# J1-3xGTHQ_R_B66.net
KiCad netlist of a schematic drawn in Altium Designer
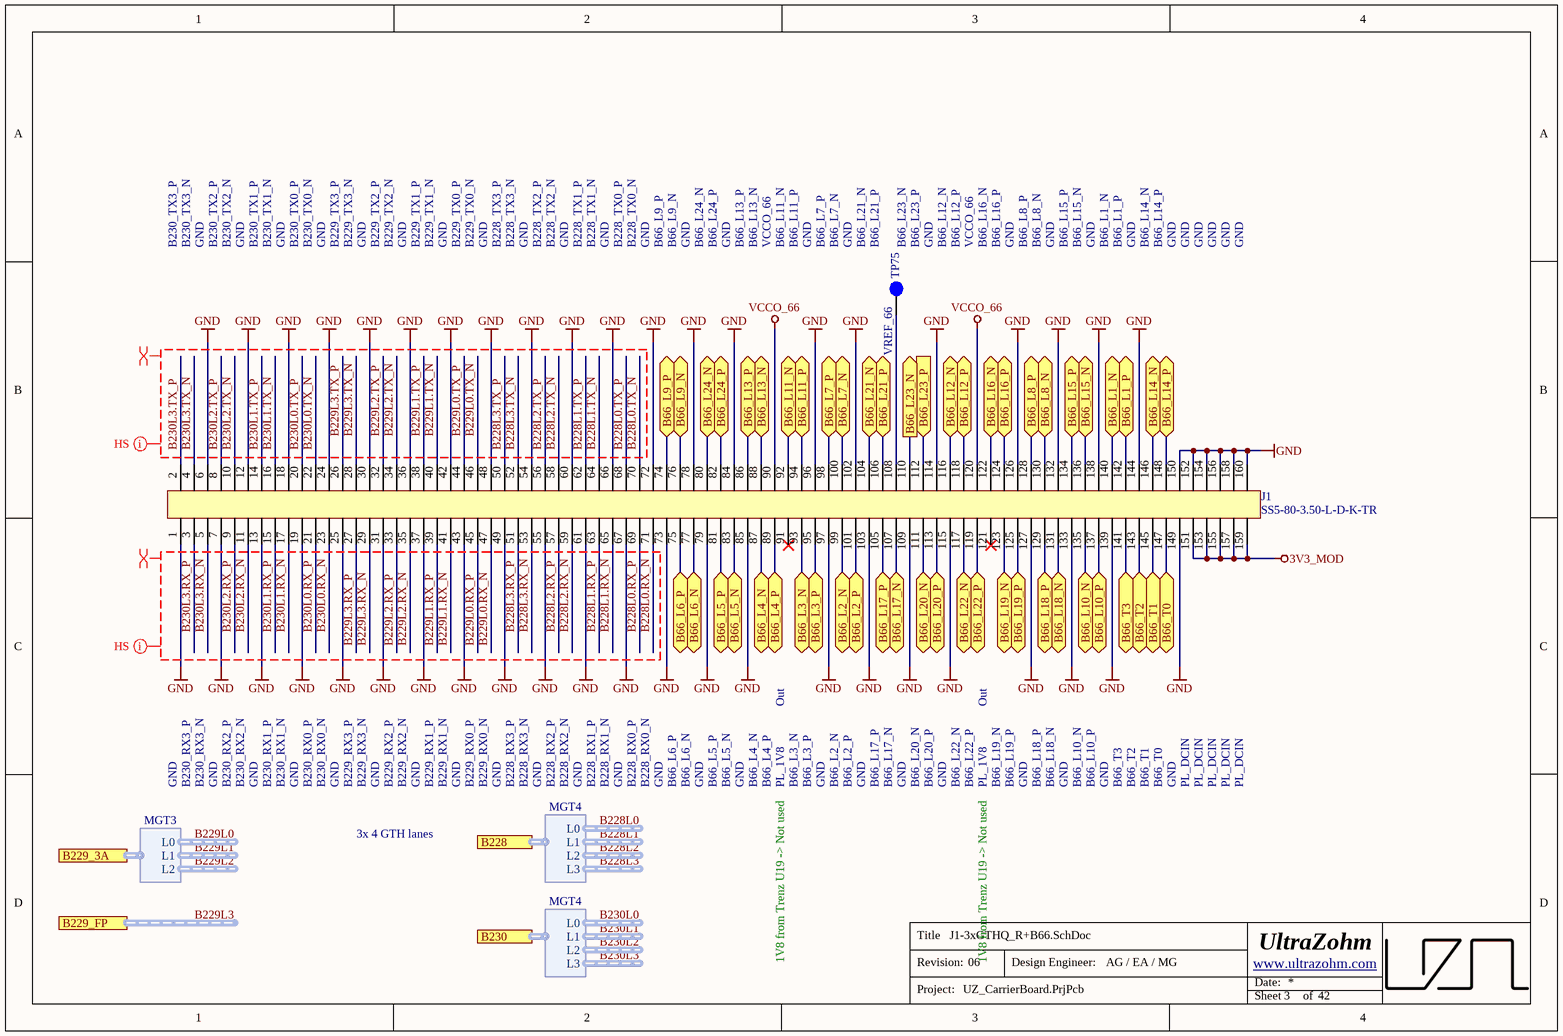
[diagram p0: J1-3xGTHQ_R+B66.SchDoc]

(export (version "E")
  (design (tool "Eeschema 10.0.6"))
  (components
    (comp (ref "J1")
      (value "SS5-80-3.50-L-D-K-TR")
      (footprint "SS5-80-3.50-L-D-K-TR")
      (description "0.5 mm Ultra Fine Pitch Socket REF192552-01, 160 Pins")
      (fields
        (field (name "MANUFACTURER") "SAMTEC")
        (field (name "LCSC PART NUMBER") "C5292077")
        (field (name "CREATED FROM") "MGremer")
      )
      (libsource (lib "user") (part "SS5-80-3.50-L-D-K-TR"))
    )
    (comp (ref "TP75") (value "Testpoint 1mm") (footprint "TP_1mm") (libsource (lib "TE") (part "TP")))
  )
  (nets
    (net (code "15") (name "/B66_L1_N") (class "Default")
      (node (ref "J1") (pin "140") (pinfunction "140_140") (pintype "passive"))
    )
    (net (code "16") (name "/B66_L1_P") (class "Default")
      (node (ref "J1") (pin "142") (pinfunction "142_142") (pintype "passive"))
    )
    (net (code "17") (name "/B66_L2_N") (class "Default")
      (node (ref "J1") (pin "99") (pinfunction "99_99") (pintype "passive"))
    )
    (net (code "18") (name "/B66_L2_P") (class "Default")
      (node (ref "J1") (pin "101") (pinfunction "101_101") (pintype "passive"))
    )
    (net (code "19") (name "/B66_L3_N") (class "Default")
      (node (ref "J1") (pin "93") (pinfunction "93_93") (pintype "passive"))
    )
    (net (code "20") (name "/B66_L3_P") (class "Default")
      (node (ref "J1") (pin "95") (pinfunction "95_95") (pintype "passive"))
    )
    (net (code "21") (name "/B66_L4_N") (class "Default")
      (node (ref "J1") (pin "87") (pinfunction "87_87") (pintype "passive"))
    )
    (net (code "22") (name "/B66_L4_P") (class "Default")
      (node (ref "J1") (pin "89") (pinfunction "89_89") (pintype "passive"))
    )
    (net (code "23") (name "/B66_L5_N") (class "Default")
      (node (ref "J1") (pin "83") (pinfunction "83_83") (pintype "passive"))
    )
    (net (code "24") (name "/B66_L5_P") (class "Default")
      (node (ref "J1") (pin "81") (pinfunction "81_81") (pintype "passive"))
    )
    (net (code "25") (name "/B66_L6_N") (class "Default")
      (node (ref "J1") (pin "77") (pinfunction "77_77") (pintype "passive"))
    )
    (net (code "26") (name "/B66_L6_P") (class "Default")
      (node (ref "J1") (pin "75") (pinfunction "75_75") (pintype "passive"))
    )
    (net (code "27") (name "/B66_L7_N") (class "Default")
      (node (ref "J1") (pin "100") (pinfunction "100_100") (pintype "passive"))
    )
    (net (code "28") (name "/B66_L7_P") (class "Default")
      (node (ref "J1") (pin "98") (pinfunction "98_98") (pintype "passive"))
    )
    (net (code "29") (name "/B66_L8_N") (class "Default")
      (node (ref "J1") (pin "130") (pinfunction "130_130") (pintype "passive"))
    )
    (net (code "30") (name "/B66_L8_P") (class "Default")
      (node (ref "J1") (pin "128") (pinfunction "128_128") (pintype "passive"))
    )
    (net (code "31") (name "/B66_L9_N") (class "Default")
      (node (ref "J1") (pin "76") (pinfunction "76_76") (pintype "passive"))
    )
    (net (code "32") (name "/B66_L9_P") (class "Default")
      (node (ref "J1") (pin "74") (pinfunction "74_74") (pintype "passive"))
    )
    (net (code "33") (name "/B66_L10_N") (class "Default")
      (node (ref "J1") (pin "135") (pinfunction "135_135") (pintype "passive"))
    )
    (net (code "34") (name "/B66_L10_P") (class "Default")
      (node (ref "J1") (pin "137") (pinfunction "137_137") (pintype "passive"))
    )
    (net (code "35") (name "/B66_L11_N") (class "Default")
      (node (ref "J1") (pin "92") (pinfunction "92_92") (pintype "passive"))
    )
    (net (code "36") (name "/B66_L11_P") (class "Default")
      (node (ref "J1") (pin "94") (pinfunction "94_94") (pintype "passive"))
    )
    (net (code "37") (name "/B66_L12_N") (class "Default")
      (node (ref "J1") (pin "116") (pinfunction "116_116") (pintype "passive"))
    )
    (net (code "38") (name "/B66_L12_P") (class "Default")
      (node (ref "J1") (pin "118") (pinfunction "118_118") (pintype "passive"))
    )
    (net (code "39") (name "/B66_L13_N") (class "Default")
      (node (ref "J1") (pin "88") (pinfunction "88_88") (pintype "passive"))
    )
    (net (code "40") (name "/B66_L13_P") (class "Default")
      (node (ref "J1") (pin "86") (pinfunction "86_86") (pintype "passive"))
    )
    (net (code "41") (name "/B66_L14_N") (class "Default")
      (node (ref "J1") (pin "146") (pinfunction "146_146") (pintype "passive"))
    )
    (net (code "42") (name "/B66_L14_P") (class "Default")
      (node (ref "J1") (pin "148") (pinfunction "148_148") (pintype "passive"))
    )
    (net (code "43") (name "/B66_L15_N") (class "Default")
      (node (ref "J1") (pin "136") (pinfunction "136_136") (pintype "passive"))
    )
    (net (code "44") (name "/B66_L15_P") (class "Default")
      (node (ref "J1") (pin "134") (pinfunction "134_134") (pintype "passive"))
    )
    (net (code "45") (name "/B66_L16_N") (class "Default")
      (node (ref "J1") (pin "122") (pinfunction "122_122") (pintype "passive"))
    )
    (net (code "46") (name "/B66_L16_P") (class "Default")
      (node (ref "J1") (pin "124") (pinfunction "124_124") (pintype "passive"))
    )
    (net (code "47") (name "/B66_L17_N") (class "Default")
      (node (ref "J1") (pin "107") (pinfunction "107_107") (pintype "passive"))
    )
    (net (code "48") (name "/B66_L17_P") (class "Default")
      (node (ref "J1") (pin "105") (pinfunction "105_105") (pintype "passive"))
    )
    (net (code "49") (name "/B66_L18_N") (class "Default")
      (node (ref "J1") (pin "131") (pinfunction "131_131") (pintype "passive"))
    )
    (net (code "50") (name "/B66_L18_P") (class "Default")
      (node (ref "J1") (pin "129") (pinfunction "129_129") (pintype "passive"))
    )
    (net (code "51") (name "/B66_L19_N") (class "Default")
      (node (ref "J1") (pin "123") (pinfunction "123_123") (pintype "passive"))
    )
    (net (code "52") (name "/B66_L19_P") (class "Default")
      (node (ref "J1") (pin "125") (pinfunction "125_125") (pintype "passive"))
    )
    (net (code "53") (name "/B66_L20_N") (class "Default")
      (node (ref "J1") (pin "111") (pinfunction "111_111") (pintype "passive"))
    )
    (net (code "54") (name "/B66_L20_P") (class "Default")
      (node (ref "J1") (pin "113") (pinfunction "113_113") (pintype "passive"))
    )
    (net (code "55") (name "/B66_L21_N") (class "Default")
      (node (ref "J1") (pin "104") (pinfunction "104_104") (pintype "passive"))
    )
    (net (code "56") (name "/B66_L21_P") (class "Default")
      (node (ref "J1") (pin "106") (pinfunction "106_106") (pintype "passive"))
    )
    (net (code "57") (name "/B66_L22_N") (class "Default")
      (node (ref "J1") (pin "117") (pinfunction "117_117") (pintype "passive"))
    )
    (net (code "58") (name "/B66_L22_P") (class "Default")
      (node (ref "J1") (pin "119") (pinfunction "119_119") (pintype "passive"))
    )
    (net (code "59") (name "/B66_L23_N") (class "Default")
      (node (ref "J1") (pin "110") (pinfunction "110_110") (pintype "passive"))
    )
    (net (code "60") (name "/B66_L23_P") (class "Default")
      (node (ref "J1") (pin "112") (pinfunction "112_112") (pintype "passive"))
    )
    (net (code "61") (name "/B66_L24_N") (class "Default")
      (node (ref "J1") (pin "80") (pinfunction "80_80") (pintype "passive"))
    )
    (net (code "62") (name "/B66_L24_P") (class "Default")
      (node (ref "J1") (pin "82") (pinfunction "82_82") (pintype "passive"))
    )
    (net (code "63") (name "/B66_T0") (class "Default")
      (node (ref "J1") (pin "147") (pinfunction "147_147") (pintype "passive"))
    )
    (net (code "64") (name "/B66_T1") (class "Default")
      (node (ref "J1") (pin "145") (pinfunction "145_145") (pintype "passive"))
    )
    (net (code "65") (name "/B66_T2") (class "Default")
      (node (ref "J1") (pin "143") (pinfunction "143_143") (pintype "passive"))
    )
    (net (code "66") (name "/B66_T3") (class "Default")
      (node (ref "J1") (pin "141") (pinfunction "141_141") (pintype "passive"))
    )
    (net (code "67") (name "/B228L0.RX_N") (class "Default")
      (node (ref "J1") (pin "71") (pinfunction "71_71") (pintype "passive"))
    )
    (net (code "68") (name "/B228L0.RX_P") (class "Default")
      (node (ref "J1") (pin "69") (pinfunction "69_69") (pintype "passive"))
    )
    (net (code "69") (name "/B228L0.TX_N") (class "Default")
      (node (ref "J1") (pin "70") (pinfunction "70_70") (pintype "passive"))
    )
    (net (code "70") (name "/B228L0.TX_P") (class "Default")
      (node (ref "J1") (pin "68") (pinfunction "68_68") (pintype "passive"))
    )
    (net (code "72") (name "/B228L1.RX_N") (class "Default")
      (node (ref "J1") (pin "65") (pinfunction "65_65") (pintype "passive"))
    )
    (net (code "73") (name "/B228L1.RX_P") (class "Default")
      (node (ref "J1") (pin "63") (pinfunction "63_63") (pintype "passive"))
    )
    (net (code "74") (name "/B228L1.TX_N") (class "Default")
      (node (ref "J1") (pin "64") (pinfunction "64_64") (pintype "passive"))
    )
    (net (code "75") (name "/B228L1.TX_P") (class "Default")
      (node (ref "J1") (pin "62") (pinfunction "62_62") (pintype "passive"))
    )
    (net (code "76") (name "/B228L2.RX_N") (class "Default")
      (node (ref "J1") (pin "59") (pinfunction "59_59") (pintype "passive"))
    )
    (net (code "77") (name "/B228L2.RX_P") (class "Default")
      (node (ref "J1") (pin "57") (pinfunction "57_57") (pintype "passive"))
    )
    (net (code "78") (name "/B228L2.TX_N") (class "Default")
      (node (ref "J1") (pin "58") (pinfunction "58_58") (pintype "passive"))
    )
    (net (code "79") (name "/B228L2.TX_P") (class "Default")
      (node (ref "J1") (pin "56") (pinfunction "56_56") (pintype "passive"))
    )
    (net (code "80") (name "/B228L3.RX_N") (class "Default")
      (node (ref "J1") (pin "53") (pinfunction "53_53") (pintype "passive"))
    )
    (net (code "81") (name "/B228L3.RX_P") (class "Default")
      (node (ref "J1") (pin "51") (pinfunction "51_51") (pintype "passive"))
    )
    (net (code "82") (name "/B228L3.TX_N") (class "Default")
      (node (ref "J1") (pin "52") (pinfunction "52_52") (pintype "passive"))
    )
    (net (code "83") (name "/B228L3.TX_P") (class "Default")
      (node (ref "J1") (pin "50") (pinfunction "50_50") (pintype "passive"))
    )
    (net (code "85") (name "/B229L0.RX_N") (class "Default")
      (node (ref "J1") (pin "47") (pinfunction "47_47") (pintype "passive"))
    )
    (net (code "86") (name "/B229L0.RX_P") (class "Default")
      (node (ref "J1") (pin "45") (pinfunction "45_45") (pintype "passive"))
    )
    (net (code "87") (name "/B229L0.TX_N") (class "Default")
      (node (ref "J1") (pin "46") (pinfunction "46_46") (pintype "passive"))
    )
    (net (code "88") (name "/B229L0.TX_P") (class "Default")
      (node (ref "J1") (pin "44") (pinfunction "44_44") (pintype "passive"))
    )
    (net (code "89") (name "/B229L1.RX_N") (class "Default")
      (node (ref "J1") (pin "41") (pinfunction "41_41") (pintype "passive"))
    )
    (net (code "90") (name "/B229L1.RX_P") (class "Default")
      (node (ref "J1") (pin "39") (pinfunction "39_39") (pintype "passive"))
    )
    (net (code "91") (name "/B229L1.TX_N") (class "Default")
      (node (ref "J1") (pin "40") (pinfunction "40_40") (pintype "passive"))
    )
    (net (code "92") (name "/B229L1.TX_P") (class "Default")
      (node (ref "J1") (pin "38") (pinfunction "38_38") (pintype "passive"))
    )
    (net (code "93") (name "/B229L2.RX_N") (class "Default")
      (node (ref "J1") (pin "35") (pinfunction "35_35") (pintype "passive"))
    )
    (net (code "94") (name "/B229L2.RX_P") (class "Default")
      (node (ref "J1") (pin "33") (pinfunction "33_33") (pintype "passive"))
    )
    (net (code "95") (name "/B229L2.TX_N") (class "Default")
      (node (ref "J1") (pin "34") (pinfunction "34_34") (pintype "passive"))
    )
    (net (code "96") (name "/B229L2.TX_P") (class "Default")
      (node (ref "J1") (pin "32") (pinfunction "32_32") (pintype "passive"))
    )
    (net (code "98") (name "/B229L3.RX_N") (class "Default")
      (node (ref "J1") (pin "29") (pinfunction "29_29") (pintype "passive"))
    )
    (net (code "99") (name "/B229L3.RX_P") (class "Default")
      (node (ref "J1") (pin "27") (pinfunction "27_27") (pintype "passive"))
    )
    (net (code "100") (name "/B229L3.TX_N") (class "Default")
      (node (ref "J1") (pin "28") (pinfunction "28_28") (pintype "passive"))
    )
    (net (code "101") (name "/B229L3.TX_P") (class "Default")
      (node (ref "J1") (pin "26") (pinfunction "26_26") (pintype "passive"))
    )
    (net (code "103") (name "/B230L0.RX_N") (class "Default")
      (node (ref "J1") (pin "23") (pinfunction "23_23") (pintype "passive"))
    )
    (net (code "104") (name "/B230L0.RX_P") (class "Default")
      (node (ref "J1") (pin "21") (pinfunction "21_21") (pintype "passive"))
    )
    (net (code "105") (name "/B230L0.TX_N") (class "Default")
      (node (ref "J1") (pin "22") (pinfunction "22_22") (pintype "passive"))
    )
    (net (code "106") (name "/B230L0.TX_P") (class "Default")
      (node (ref "J1") (pin "20") (pinfunction "20_20") (pintype "passive"))
    )
    (net (code "108") (name "/B230L1.RX_N") (class "Default")
      (node (ref "J1") (pin "17") (pinfunction "17_17") (pintype "passive"))
    )
    (net (code "109") (name "/B230L1.RX_P") (class "Default")
      (node (ref "J1") (pin "15") (pinfunction "15_15") (pintype "passive"))
    )
    (net (code "110") (name "/B230L1.TX_N") (class "Default")
      (node (ref "J1") (pin "16") (pinfunction "16_16") (pintype "passive"))
    )
    (net (code "111") (name "/B230L1.TX_P") (class "Default")
      (node (ref "J1") (pin "14") (pinfunction "14_14") (pintype "passive"))
    )
    (net (code "112") (name "/B230L2.RX_N") (class "Default")
      (node (ref "J1") (pin "11") (pinfunction "11_11") (pintype "passive"))
    )
    (net (code "113") (name "/B230L2.RX_P") (class "Default")
      (node (ref "J1") (pin "9") (pinfunction "9_9") (pintype "passive"))
    )
    (net (code "114") (name "/B230L2.TX_N") (class "Default")
      (node (ref "J1") (pin "10") (pinfunction "10_10") (pintype "passive"))
    )
    (net (code "115") (name "/B230L2.TX_P") (class "Default")
      (node (ref "J1") (pin "8") (pinfunction "8_8") (pintype "passive"))
    )
    (net (code "116") (name "/B230L3.RX_N") (class "Default")
      (node (ref "J1") (pin "5") (pinfunction "5_5") (pintype "passive"))
    )
    (net (code "117") (name "/B230L3.RX_P") (class "Default")
      (node (ref "J1") (pin "3") (pinfunction "3_3") (pintype "passive"))
    )
    (net (code "118") (name "/B230L3.TX_N") (class "Default")
      (node (ref "J1") (pin "4") (pinfunction "4_4") (pintype "passive"))
    )
    (net (code "119") (name "/B230L3.TX_P") (class "Default")
      (node (ref "J1") (pin "2") (pinfunction "2_2") (pintype "passive"))
    )
    (net (code "129") (name "3V3_MOD") (class "Default")
      (node (ref "J1") (pin "151") (pinfunction "151_151") (pintype "passive"))
      (node (ref "J1") (pin "153") (pinfunction "153_153") (pintype "passive"))
      (node (ref "J1") (pin "155") (pinfunction "155_155") (pintype "passive"))
      (node (ref "J1") (pin "157") (pinfunction "157_157") (pintype "passive"))
      (node (ref "J1") (pin "159") (pinfunction "159_159") (pintype "passive"))
    )
    (net (code "130") (name "GND") (class "Default")
      (node (ref "J1") (pin "1") (pinfunction "1_1") (pintype "passive"))
      (node (ref "J1") (pin "102") (pinfunction "102_102") (pintype "passive"))
      (node (ref "J1") (pin "103") (pinfunction "103_103") (pintype "passive"))
      (node (ref "J1") (pin "109") (pinfunction "109_109") (pintype "passive"))
      (node (ref "J1") (pin "114") (pinfunction "114_114") (pintype "passive"))
      (node (ref "J1") (pin "115") (pinfunction "115_115") (pintype "passive"))
      (node (ref "J1") (pin "12") (pinfunction "12_12") (pintype "passive"))
      (node (ref "J1") (pin "126") (pinfunction "126_126") (pintype "passive"))
      (node (ref "J1") (pin "127") (pinfunction "127_127") (pintype "passive"))
      (node (ref "J1") (pin "13") (pinfunction "13_13") (pintype "passive"))
      (node (ref "J1") (pin "132") (pinfunction "132_132") (pintype "passive"))
      (node (ref "J1") (pin "133") (pinfunction "133_133") (pintype "passive"))
      (node (ref "J1") (pin "138") (pinfunction "138_138") (pintype "passive"))
      (node (ref "J1") (pin "139") (pinfunction "139_139") (pintype "passive"))
      (node (ref "J1") (pin "144") (pinfunction "144_144") (pintype "passive"))
      (node (ref "J1") (pin "149") (pinfunction "149_149") (pintype "passive"))
      (node (ref "J1") (pin "150") (pinfunction "150_150") (pintype "passive"))
      (node (ref "J1") (pin "152") (pinfunction "152_152") (pintype "passive"))
      (node (ref "J1") (pin "154") (pinfunction "154_154") (pintype "passive"))
      (node (ref "J1") (pin "156") (pinfunction "156_156") (pintype "passive"))
      (node (ref "J1") (pin "158") (pinfunction "158_158") (pintype "passive"))
      (node (ref "J1") (pin "160") (pinfunction "160_160") (pintype "passive"))
      (node (ref "J1") (pin "18") (pinfunction "18_18") (pintype "passive"))
      (node (ref "J1") (pin "19") (pinfunction "19_19") (pintype "passive"))
      (node (ref "J1") (pin "24") (pinfunction "24_24") (pintype "passive"))
      (node (ref "J1") (pin "25") (pinfunction "25_25") (pintype "passive"))
      (node (ref "J1") (pin "30") (pinfunction "30_30") (pintype "passive"))
      (node (ref "J1") (pin "31") (pinfunction "31_31") (pintype "passive"))
      (node (ref "J1") (pin "36") (pinfunction "36_36") (pintype "passive"))
      (node (ref "J1") (pin "37") (pinfunction "37_37") (pintype "passive"))
      (node (ref "J1") (pin "42") (pinfunction "42_42") (pintype "passive"))
      (node (ref "J1") (pin "43") (pinfunction "43_43") (pintype "passive"))
      (node (ref "J1") (pin "48") (pinfunction "48_48") (pintype "passive"))
      (node (ref "J1") (pin "49") (pinfunction "49_49") (pintype "passive"))
      (node (ref "J1") (pin "54") (pinfunction "54_54") (pintype "passive"))
      (node (ref "J1") (pin "55") (pinfunction "55_55") (pintype "passive"))
      (node (ref "J1") (pin "6") (pinfunction "6_6") (pintype "passive"))
      (node (ref "J1") (pin "60") (pinfunction "60_60") (pintype "passive"))
      (node (ref "J1") (pin "61") (pinfunction "61_61") (pintype "passive"))
      (node (ref "J1") (pin "66") (pinfunction "66_66") (pintype "passive"))
      (node (ref "J1") (pin "67") (pinfunction "67_67") (pintype "passive"))
      (node (ref "J1") (pin "7") (pinfunction "7_7") (pintype "passive"))
      (node (ref "J1") (pin "72") (pinfunction "72_72") (pintype "passive"))
      (node (ref "J1") (pin "73") (pinfunction "73_73") (pintype "passive"))
      (node (ref "J1") (pin "78") (pinfunction "78_78") (pintype "passive"))
      (node (ref "J1") (pin "79") (pinfunction "79_79") (pintype "passive"))
      (node (ref "J1") (pin "84") (pinfunction "84_84") (pintype "passive"))
      (node (ref "J1") (pin "85") (pinfunction "85_85") (pintype "passive"))
      (node (ref "J1") (pin "96") (pinfunction "96_96") (pintype "passive"))
      (node (ref "J1") (pin "97") (pinfunction "97_97") (pintype "passive"))
    )
    (net (code "131") (name "Net-(J1-Pad108)") (class "Default")
      (node (ref "J1") (pin "108") (pinfunction "108_108") (pintype "passive"))
      (node (ref "TP75") (pin "1") (pintype "passive"))
    )
    (net (code "132") (name "VCCO_66") (class "Default")
      (node (ref "J1") (pin "120") (pinfunction "120_120") (pintype "passive"))
      (node (ref "J1") (pin "90") (pinfunction "90_90") (pintype "passive"))
    )
    (net (code "133") (name "unconnected-(J1-Pad91)") (class "Default")
      (node (ref "J1") (pin "91") (pinfunction "91_91") (pintype "passive+no_connect"))
    )
    (net (code "134") (name "unconnected-(J1-Pad121)") (class "Default")
      (node (ref "J1") (pin "121") (pinfunction "121_121") (pintype "passive+no_connect"))
    )
  )
)
